# Buck_Converter.net
KiCad netlist of a schematic drawn in Altium Designer
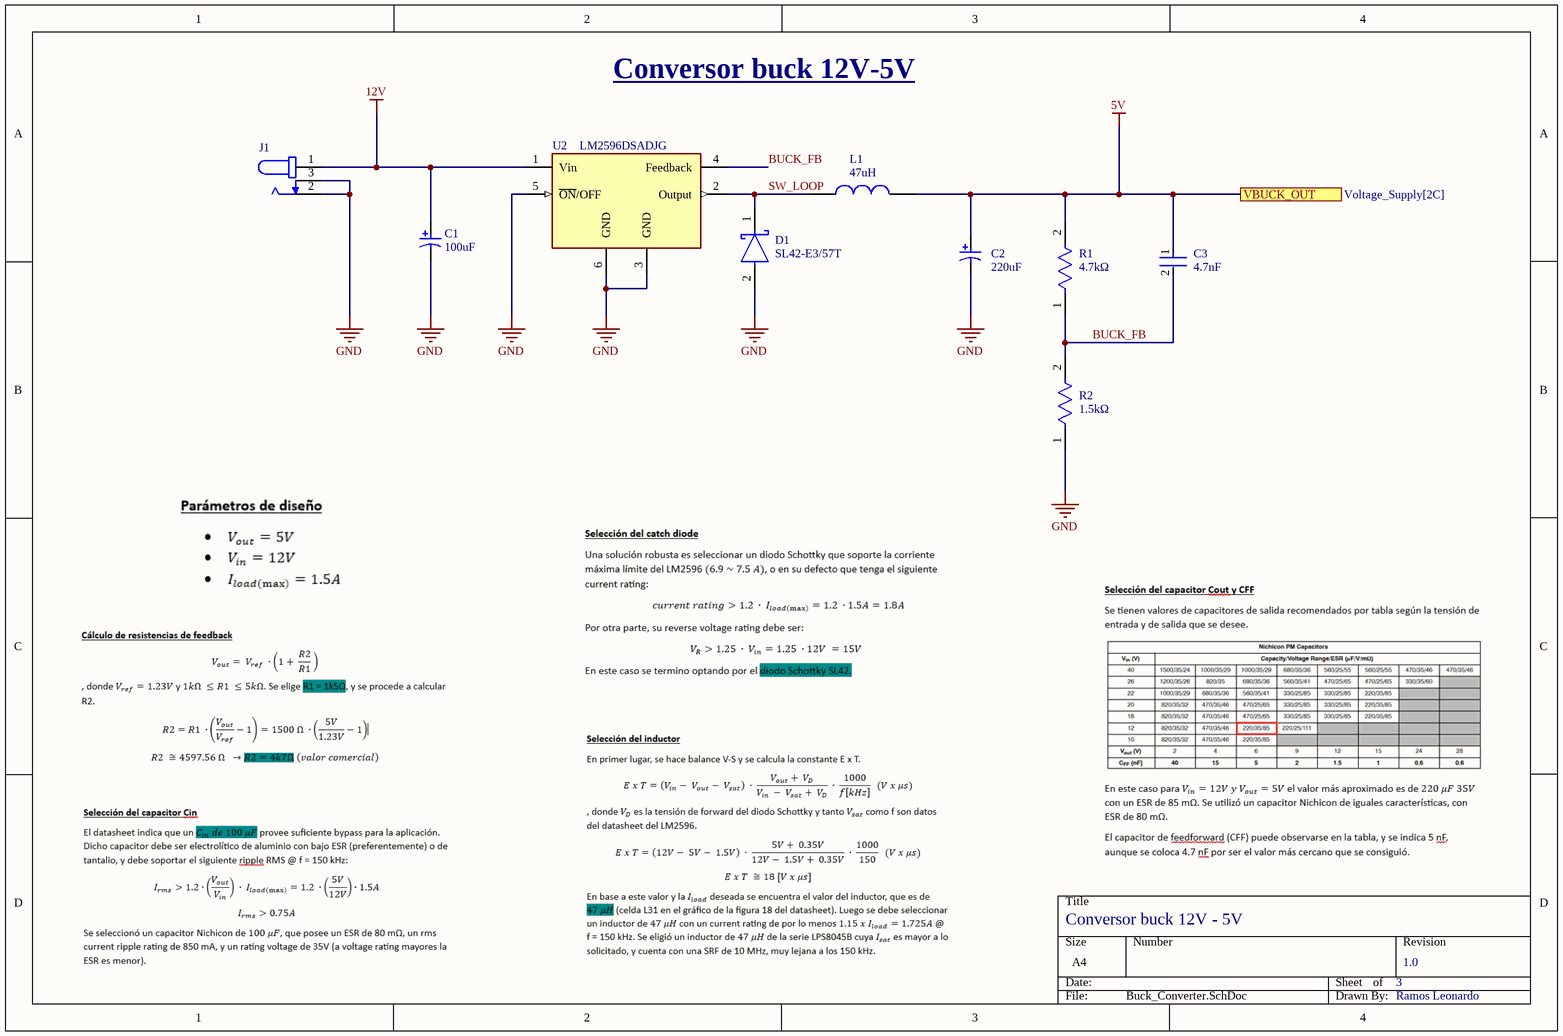
[diagram p0: Buck_Converter.SchDoc]

(export (version "E")
  (design (tool "Eeschema 10.0.6"))
  (components
    (comp (ref "C1")
      (value "UCL1V101MNL1GS")
      (footprint "NIC-UCL1V101MNL1GS_L")
      (fields
        (field (name "CAPACITANCE") "100uF")
        (field (name "MANUFACTURER") "Nichicon")
        (field (name "TOLERANCE") "20%")
      )
      (libsource (lib "Altium Content Vault") (part "CAP-P-2"))
    )
    (comp (ref "C2")
      (value "UCL1V101MNL1GS")
      (footprint "NIC-UCL1V101MNL1GS_L")
      (fields
        (field (name "CAPACITANCE") "220uF")
        (field (name "MANUFACTURER") "Nichicon")
        (field (name "TOLERANCE") "20%")
      )
      (libsource (lib "Altium Content Vault") (part "CAP-P-2"))
    )
    (comp (ref "C3")
      (value "GRM21B7U1A104JA01L")
      (footprint "FP-GRM21B-0_1-IPC_B")
      (description "Chip Multilayer Ceramic Capacitors for General Purpose, 0805, 4.7nF, U2J, -750ppm/°C, 5%, 10V")
      (fields (field (name "CAPACITANCE") "4.7nF") (field (name "TOLERANCE") "5%"))
      (libsource (lib "Altium Content Vault") (part "b4654b650e69147ec39a6b967a45e02"))
    )
    (comp (ref "D1")
      (value "SL42-E3/57T")
      (footprint "FP-95402-MFG")
      (description "SL42-E3/57T Rectifier Diode, Schottky, 1 Phase, 1 Element, 4A, 20V V(RRM), Silicon, DO-214AB")
      (libsource (lib "Altium Content Vault") (part "c1678fac7984e62e0809fbf79c06691"))
    )
    (comp (ref "J1")
      (value "DCJ200-10-A-XX-K_REVA")
      (footprint "GCT_DCJ200-10-A-XX-K_REVA")
      (description "Power Barrel Connector Jack 2.05mm ID (0.081), 5.50mm OD (0.217) Through Hole, Right Angle")
      (fields (field (name "MF") "Global Connector Technology") (field (name "MP") "DCJ200-10-A-K1-K"))
      (libsource (lib "Componentes_custom") (part "DCJ200-10-A-XX-K_REVA"))
    )
    (comp (ref "L1")
      (value "47uH")
      (footprint "LPS8045B_Series_Power_inductor")
      (description "Inductor genérico")
      (libsource (lib "Componentes_custom") (part "L"))
    )
    (comp (ref "R1")
      (value "CRCW08054K70JNEA")
      (footprint "FP-CRCW0805-e3-IPC_B")
      (description "RES Thick Film, 1.5kΩ, 5%, 0.125W, 200ppm/°C, 0805")
      (fields (field (name "TOLERANCE") "5%") (field (name "RESISTANCE") "4.7kΩ"))
      (libsource (lib "Altium Content Vault") (part "1029c3af85768c4190bb7ad29bc67b5"))
    )
    (comp (ref "R2")
      (value "CRCW08054K70JNEA")
      (footprint "FP-CRCW0805-e3-IPC_B")
      (description "RES Thick Film, 4.7kΩ, 5%, 0.125W, 200ppm/°C, 0805")
      (fields (field (name "TOLERANCE") "5%") (field (name "RESISTANCE") "1.5kΩ"))
      (libsource (lib "Altium Content Vault") (part "1029c3af85768c4190bb7ad29bc67b5"))
    )
    (comp (ref "U2")
      (value "LM2596DSADJG")
      (footprint "FP-936A-02-MFG")
      (description "IC REG MULT CONFG ADJ 3A D2PAK-5")
      (fields
        (field (name "OCTOPART") "https://octopart.com/lm2596dsadjg-on+semiconductor-12437034")
        (field (name "MANUFACTURER") "ON Semiconductor")
      )
      (libsource (lib "Altium Content Vault") (part "6e009c68f80b765d55aa2e30e527964"))
    )
  )
  (nets
    (net (code "1") (name "/BUCK_FB") (class "Default")
      (node (ref "C3") (pin "2") (pinfunction "2_2") (pintype "passive"))
      (node (ref "R1") (pin "1") (pinfunction "1_1") (pintype "passive"))
      (node (ref "R2") (pin "2") (pinfunction "2_2") (pintype "passive"))
      (node (ref "U2") (pin "4") (pinfunction "Feedback_4") (pintype "passive"))
    )
    (net (code "2") (name "/SW_LOOP") (class "Default")
      (node (ref "D1") (pin "1") (pinfunction "C_1") (pintype "passive"))
      (node (ref "L1") (pin "1") (pintype "passive"))
      (node (ref "U2") (pin "2") (pinfunction "Output_2") (pintype "output"))
    )
    (net (code "3") (name "5V") (class "Default")
      (node (ref "C2") (pin "1") (pinfunction "1_1") (pintype "passive"))
      (node (ref "C3") (pin "1") (pinfunction "1_1") (pintype "passive"))
      (node (ref "L1") (pin "2") (pintype "passive"))
      (node (ref "R1") (pin "2") (pinfunction "2_2") (pintype "passive"))
    )
    (net (code "4") (name "12V") (class "Default")
      (node (ref "C1") (pin "1") (pinfunction "1_1") (pintype "passive"))
      (node (ref "J1") (pin "1") (pinfunction "1_1") (pintype "passive"))
      (node (ref "U2") (pin "1") (pinfunction "Vin_1") (pintype "power_in"))
    )
    (net (code "5") (name "GND") (class "Default")
      (node (ref "C1") (pin "2") (pinfunction "2_2") (pintype "passive"))
      (node (ref "C2") (pin "2") (pinfunction "2_2") (pintype "passive"))
      (node (ref "D1") (pin "2") (pinfunction "A_2") (pintype "passive"))
      (node (ref "J1") (pin "2") (pinfunction "2_2") (pintype "passive"))
      (node (ref "J1") (pin "3") (pinfunction "3_3") (pintype "passive"))
      (node (ref "R2") (pin "1") (pinfunction "1_1") (pintype "passive"))
      (node (ref "U2") (pin "3") (pinfunction "GND_3") (pintype "power_in"))
      (node (ref "U2") (pin "5") (pinfunction "~{ON}/OFF_5") (pintype "input"))
      (node (ref "U2") (pin "6") (pinfunction "GND_6") (pintype "power_in"))
    )
  )
)
